# WL-FPGA.net
KiCad netlist of a schematic drawn in Altium Designer
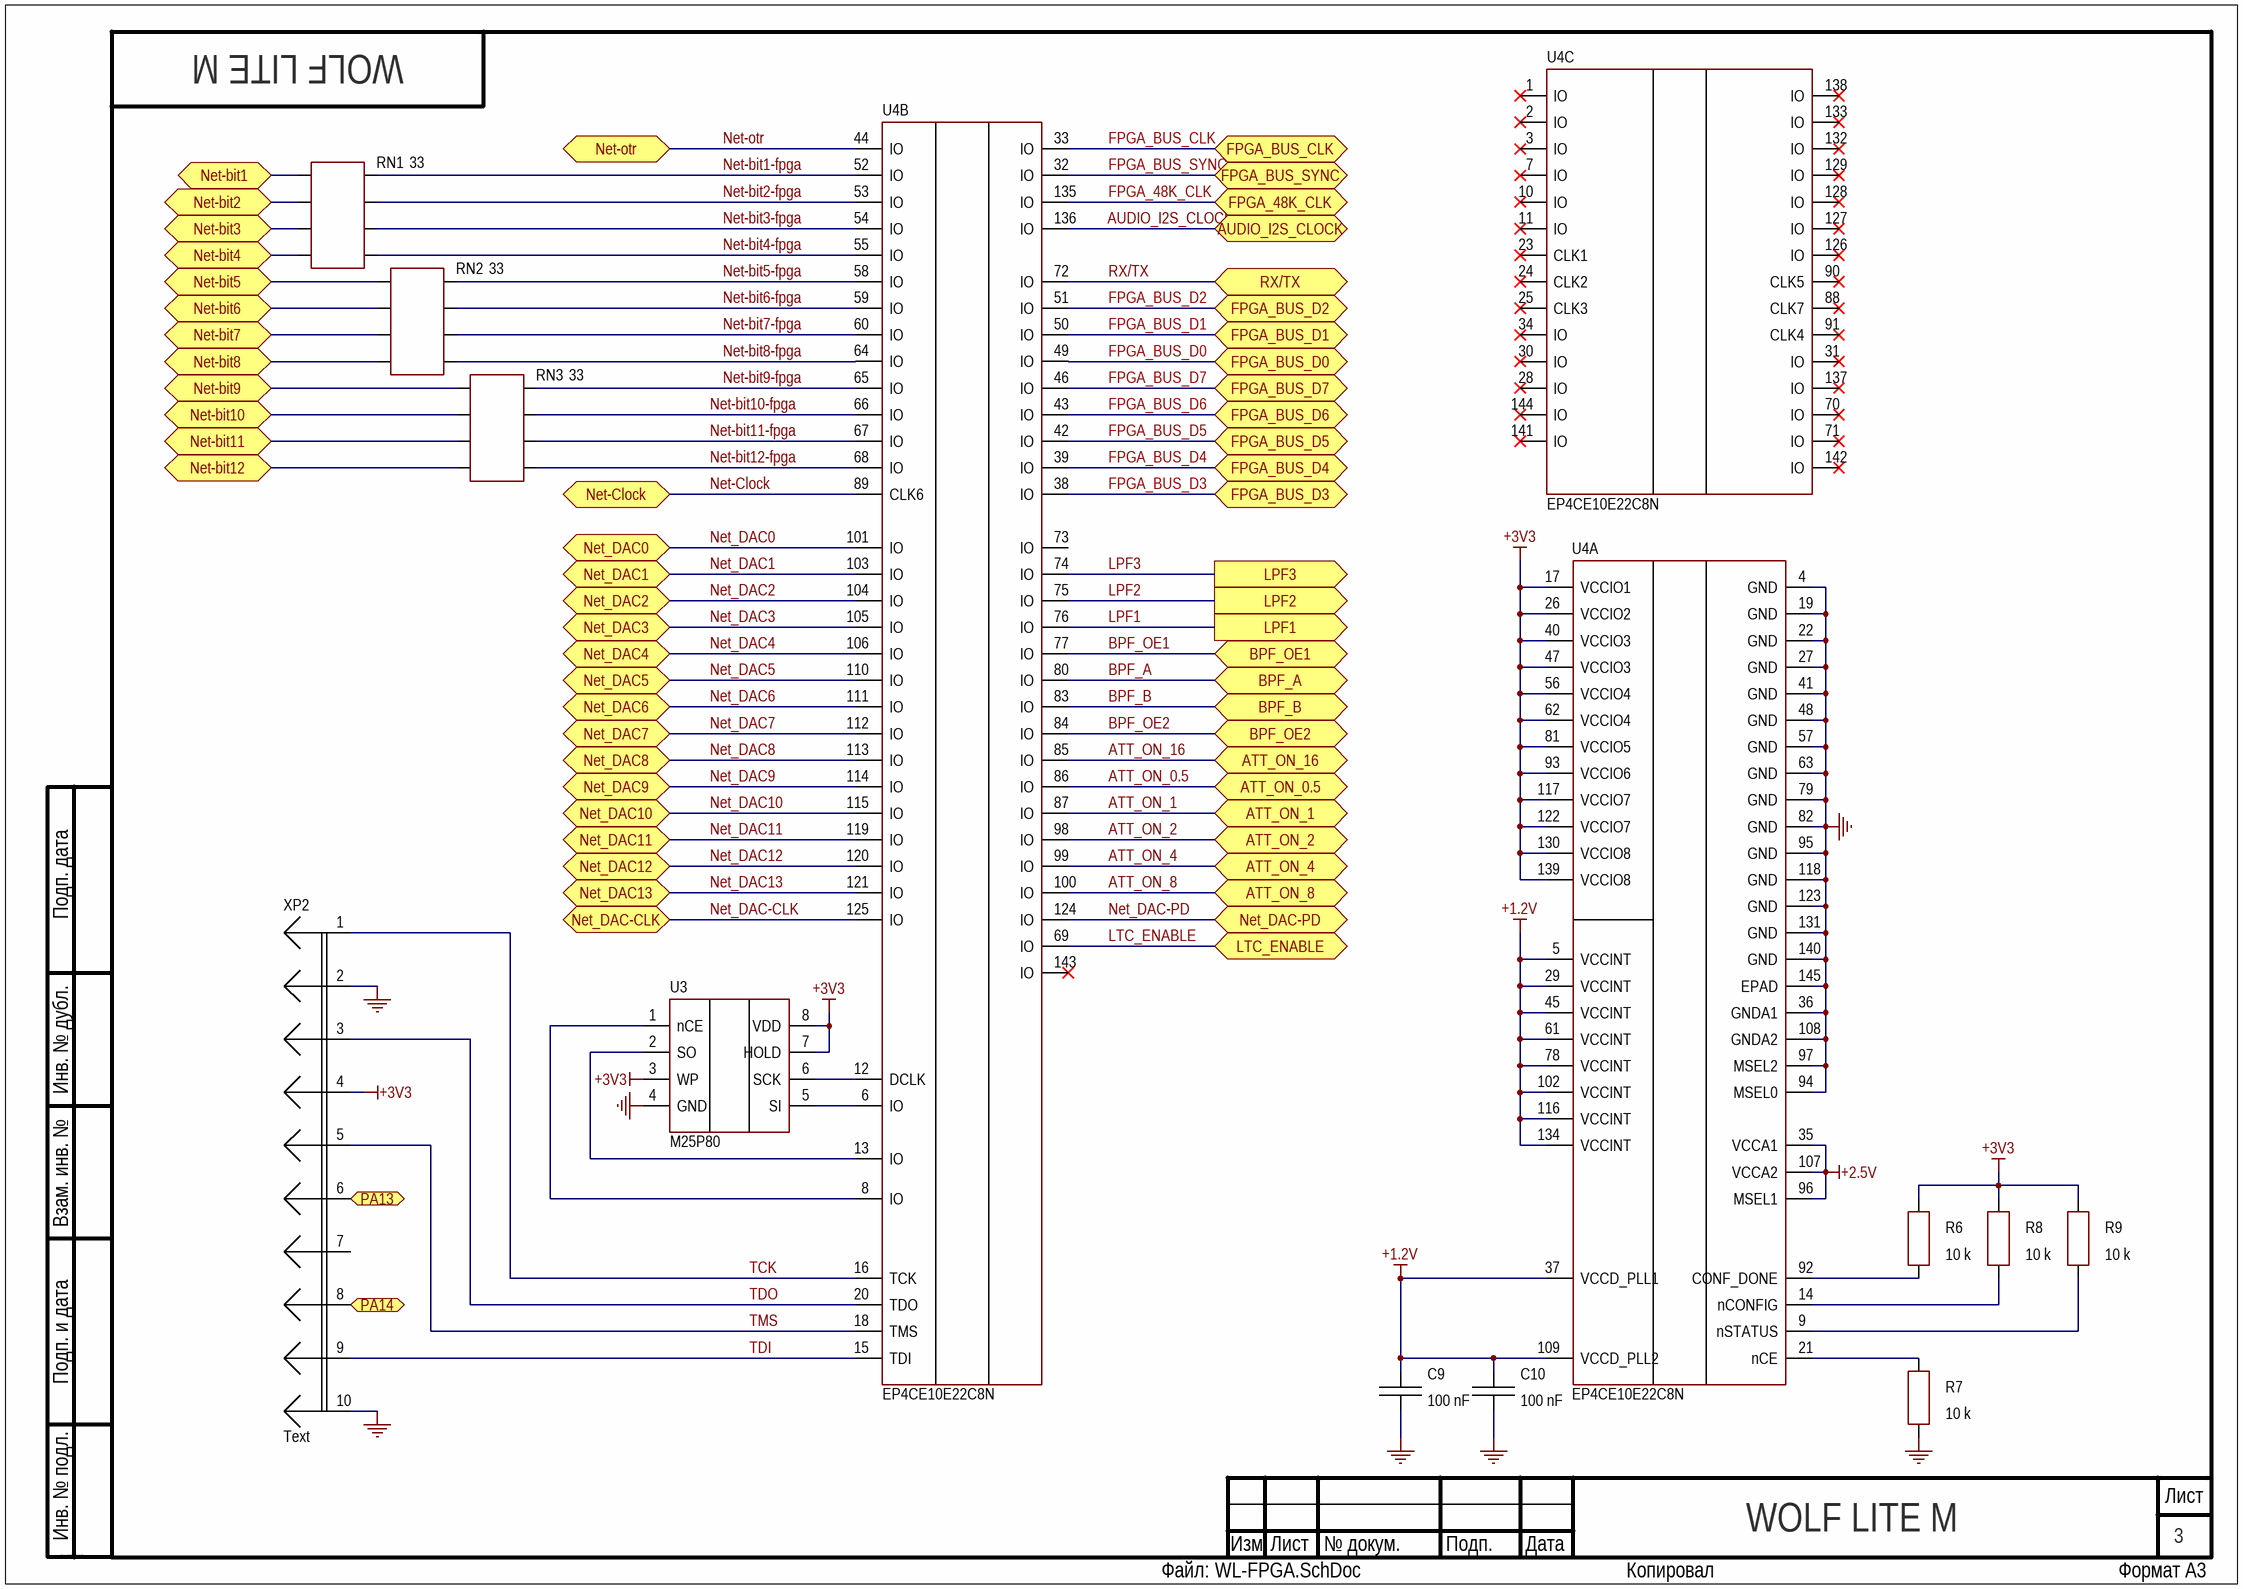
[diagram p0: WL-FPGA.SchDoc]

(export (version "E")
  (design (tool "Eeschema 10.0.6"))
  (components
    (comp (ref "C9")
      (value "100 nF")
      (footprint "C-0805-0.95")
      (fields
        (field (name "MANUFACTURER") "Yageo")
        (field (name "PART NUMBER") "CC0805KRX7R9BB104")
        (field (name "TOLERANCE") "±10%")
      )
      (libsource (lib "GOST") (part "Capacitor"))
    )
    (comp (ref "C10")
      (value "100 nF")
      (footprint "C-0805-0.95")
      (fields
        (field (name "MANUFACTURER") "Yageo")
        (field (name "PART NUMBER") "CC0805KRX7R9BB104")
        (field (name "TOLERANCE") "±10%")
      )
      (libsource (lib "GOST") (part "Capacitor"))
    )
    (comp (ref "R6")
      (value "10 k")
      (footprint "R-0805")
      (fields
        (field (name "MANUFACTURER") "Yageo")
        (field (name "PART NUMBER") "RC0805JR-0710KL")
        (field (name "POWER") "0,125 W")
      )
      (libsource (lib "GOST") (part "Resistor"))
    )
    (comp (ref "R7")
      (value "10 k")
      (footprint "R-0805")
      (fields
        (field (name "MANUFACTURER") "Yageo")
        (field (name "PART NUMBER") "RC0805JR-0710KL")
        (field (name "POWER") "0,125 W")
      )
      (libsource (lib "") (part "Resistor_1"))
    )
    (comp (ref "R8")
      (value "10 k")
      (footprint "R-0805")
      (fields
        (field (name "MANUFACTURER") "Yageo")
        (field (name "PART NUMBER") "RC0805JR-0710KL")
        (field (name "POWER") "0,125 W")
      )
      (libsource (lib "GOST") (part "Resistor"))
    )
    (comp (ref "R9")
      (value "10 k")
      (footprint "R-0805")
      (fields
        (field (name "MANUFACTURER") "Yageo")
        (field (name "PART NUMBER") "RC0805JR-0710KL")
        (field (name "POWER") "0,125 W")
      )
      (libsource (lib "GOST") (part "Resistor"))
    )
    (comp (ref "RN1")
      (value "33")
      (footprint "RN-1206")
      (fields
        (field (name "PART NUMBER") "YC164-JR-0733RL")
        (field (name "POWER") "1/16W")
        (field (name "TOLERANCE") "±5%")
      )
      (libsource (lib "GOST") (part "Resistor array"))
    )
    (comp (ref "RN2")
      (value "33")
      (footprint "RN-1206")
      (fields
        (field (name "PART NUMBER") "YC164-JR-0733RL")
        (field (name "POWER") "1/16W")
        (field (name "TOLERANCE") "±5%")
      )
      (libsource (lib "GOST") (part "Resistor array"))
    )
    (comp (ref "RN3")
      (value "33")
      (footprint "RN-1206")
      (fields
        (field (name "PART NUMBER") "YC164-JR-0733RL")
        (field (name "POWER") "1/16W")
        (field (name "TOLERANCE") "±5%")
      )
      (libsource (lib "GOST") (part "Resistor array"))
    )
    (comp (ref "U3")
      (value "M25P80")
      (footprint "SOIC-8-W")
      (description "IC FLASH 8MBIT SPI 75MHZ")
      (fields
        (field (name "PART NUMBER") "M25P80-VMW6")
        (field (name "MANUFACTURER") "Micron Technology Inc.")
      )
      (libsource (lib "GOST") (part "M25P80-VMN6TPBA TR"))
    )
    (comp (ref "U4")
      (value "EP4CE10E22C8N")
      (footprint "EQFP-144")
      (fields (field (name "MANUFACTURER") "Intel"))
      (libsource (lib "") (part "EP4CE10E22C8N_1"))
    )
    (comp (ref "XP2")
      (value "Text")
      (footprint "PLD-10-JTAG-FPGA-SWD")
      (fields (field (name "PART NUMBER") "PLD-10"))
      (libsource (lib "GOST") (part "Con-10-M"))
    )
  )
  (nets
    (net (code "1") (name "+1.2V") (class "Default")
      (node (ref "C10") (pin "2") (pinfunction "2_2") (pintype "passive"))
      (node (ref "C9") (pin "2") (pinfunction "2_2") (pintype "passive"))
      (node (ref "U4") (pin "102") (pinfunction "VCCINT_102") (pintype "passive"))
      (node (ref "U4") (pin "109") (pinfunction "VCCD_PLL2_109") (pintype "passive"))
      (node (ref "U4") (pin "116") (pinfunction "VCCINT_116") (pintype "passive"))
      (node (ref "U4") (pin "134") (pinfunction "VCCINT_134") (pintype "passive"))
      (node (ref "U4") (pin "29") (pinfunction "VCCINT_29") (pintype "passive"))
      (node (ref "U4") (pin "37") (pinfunction "VCCD_PLL1_37") (pintype "passive"))
      (node (ref "U4") (pin "45") (pinfunction "VCCINT_45") (pintype "passive"))
      (node (ref "U4") (pin "5") (pinfunction "VCCINT_5") (pintype "passive"))
      (node (ref "U4") (pin "61") (pinfunction "VCCINT_61") (pintype "passive"))
      (node (ref "U4") (pin "78") (pinfunction "VCCINT_78") (pintype "passive"))
    )
    (net (code "2") (name "+2.5V") (class "Default")
      (node (ref "U4") (pin "107") (pinfunction "VCCA2_107") (pintype "passive"))
      (node (ref "U4") (pin "35") (pinfunction "VCCA1_35") (pintype "passive"))
      (node (ref "U4") (pin "96") (pinfunction "MSEL1_96") (pintype "passive"))
    )
    (net (code "3") (name "+3V3") (class "Default")
      (node (ref "R6") (pin "1") (pinfunction "1_1") (pintype "passive"))
      (node (ref "R8") (pin "1") (pinfunction "1_1") (pintype "passive"))
      (node (ref "R9") (pin "1") (pinfunction "1_1") (pintype "passive"))
      (node (ref "U3") (pin "3") (pinfunction "WP_3") (pintype "passive"))
      (node (ref "U3") (pin "7") (pinfunction "HOLD_7") (pintype "passive"))
      (node (ref "U3") (pin "8") (pinfunction "VDD_8") (pintype "passive"))
      (node (ref "U4") (pin "117") (pinfunction "VCCIO7_117") (pintype "passive"))
      (node (ref "U4") (pin "122") (pinfunction "VCCIO7_122") (pintype "passive"))
      (node (ref "U4") (pin "130") (pinfunction "VCCIO8_130") (pintype "passive"))
      (node (ref "U4") (pin "139") (pinfunction "VCCIO8_139") (pintype "passive"))
      (node (ref "U4") (pin "17") (pinfunction "VCCIO1_17") (pintype "passive"))
      (node (ref "U4") (pin "26") (pinfunction "VCCIO2_26") (pintype "passive"))
      (node (ref "U4") (pin "40") (pinfunction "VCCIO3_40") (pintype "passive"))
      (node (ref "U4") (pin "47") (pinfunction "VCCIO3_47") (pintype "passive"))
      (node (ref "U4") (pin "56") (pinfunction "VCCIO4_56") (pintype "passive"))
      (node (ref "U4") (pin "62") (pinfunction "VCCIO4_62") (pintype "passive"))
      (node (ref "U4") (pin "81") (pinfunction "VCCIO5_81") (pintype "passive"))
      (node (ref "U4") (pin "93") (pinfunction "VCCIO6_93") (pintype "passive"))
      (node (ref "XP2") (pin "4") (pintype "passive"))
    )
    (net (code "4") (name "/ATT_ON_0.5") (class "Default")
      (node (ref "U4") (pin "86") (pinfunction "IO_86") (pintype "passive"))
    )
    (net (code "5") (name "/ATT_ON_1") (class "Default")
      (node (ref "U4") (pin "87") (pinfunction "IO_87") (pintype "passive"))
    )
    (net (code "6") (name "/ATT_ON_2") (class "Default")
      (node (ref "U4") (pin "98") (pinfunction "IO_98") (pintype "passive"))
    )
    (net (code "7") (name "/ATT_ON_4") (class "Default")
      (node (ref "U4") (pin "99") (pinfunction "IO_99") (pintype "passive"))
    )
    (net (code "8") (name "/ATT_ON_8") (class "Default")
      (node (ref "U4") (pin "100") (pinfunction "IO_100") (pintype "passive"))
    )
    (net (code "9") (name "/ATT_ON_16") (class "Default")
      (node (ref "U4") (pin "85") (pinfunction "IO_85") (pintype "passive"))
    )
    (net (code "10") (name "/AUDIO_I2S_CLOCK") (class "Default")
      (node (ref "U4") (pin "136") (pinfunction "IO_136") (pintype "passive"))
    )
    (net (code "11") (name "/BPF_A") (class "Default")
      (node (ref "U4") (pin "80") (pinfunction "IO_80") (pintype "passive"))
    )
    (net (code "12") (name "/BPF_B") (class "Default")
      (node (ref "U4") (pin "83") (pinfunction "IO_83") (pintype "passive"))
    )
    (net (code "13") (name "/BPF_OE1") (class "Default")
      (node (ref "U4") (pin "77") (pinfunction "IO_77") (pintype "passive"))
    )
    (net (code "14") (name "/BPF_OE2") (class "Default")
      (node (ref "U4") (pin "84") (pinfunction "IO_84") (pintype "passive"))
    )
    (net (code "15") (name "/FPGA_48K_CLK") (class "Default")
      (node (ref "U4") (pin "135") (pinfunction "IO_135") (pintype "passive"))
    )
    (net (code "16") (name "/FPGA_BUS_CLK") (class "Default")
      (node (ref "U4") (pin "33") (pinfunction "IO_33") (pintype "passive"))
    )
    (net (code "17") (name "/FPGA_BUS_D0") (class "Default")
      (node (ref "U4") (pin "49") (pinfunction "IO_49") (pintype "passive"))
    )
    (net (code "18") (name "/FPGA_BUS_D1") (class "Default")
      (node (ref "U4") (pin "50") (pinfunction "IO_50") (pintype "passive"))
    )
    (net (code "19") (name "/FPGA_BUS_D2") (class "Default")
      (node (ref "U4") (pin "51") (pinfunction "IO_51") (pintype "passive"))
    )
    (net (code "20") (name "/FPGA_BUS_D3") (class "Default")
      (node (ref "U4") (pin "38") (pinfunction "IO_38") (pintype "passive"))
    )
    (net (code "21") (name "/FPGA_BUS_D4") (class "Default")
      (node (ref "U4") (pin "39") (pinfunction "IO_39") (pintype "passive"))
    )
    (net (code "22") (name "/FPGA_BUS_D5") (class "Default")
      (node (ref "U4") (pin "42") (pinfunction "IO_42") (pintype "passive"))
    )
    (net (code "23") (name "/FPGA_BUS_D6") (class "Default")
      (node (ref "U4") (pin "43") (pinfunction "IO_43") (pintype "passive"))
    )
    (net (code "24") (name "/FPGA_BUS_D7") (class "Default")
      (node (ref "U4") (pin "46") (pinfunction "IO_46") (pintype "passive"))
    )
    (net (code "25") (name "/FPGA_BUS_SYNC") (class "Default")
      (node (ref "U4") (pin "32") (pinfunction "IO_32") (pintype "passive"))
    )
    (net (code "26") (name "/LPF1") (class "Default")
      (node (ref "U4") (pin "76") (pinfunction "IO_76") (pintype "passive"))
    )
    (net (code "27") (name "/LPF2") (class "Default")
      (node (ref "U4") (pin "75") (pinfunction "IO_75") (pintype "passive"))
    )
    (net (code "28") (name "/LPF3") (class "Default")
      (node (ref "U4") (pin "74") (pinfunction "IO_74") (pintype "passive"))
    )
    (net (code "29") (name "/LTC_ENABLE") (class "Default")
      (node (ref "U4") (pin "69") (pinfunction "IO_69") (pintype "passive"))
    )
    (net (code "30") (name "/Net-Clock") (class "Default")
      (node (ref "U4") (pin "89") (pinfunction "CLK6_89") (pintype "passive"))
    )
    (net (code "31") (name "/Net-bit1") (class "Default")
      (node (ref "RN1") (pin "1") (pinfunction "1_1") (pintype "passive"))
    )
    (net (code "32") (name "/Net-bit1-fpga") (class "Default")
      (node (ref "RN1") (pin "8") (pinfunction "8_8") (pintype "passive"))
      (node (ref "U4") (pin "52") (pinfunction "IO_52") (pintype "passive"))
    )
    (net (code "33") (name "/Net-bit2") (class "Default")
      (node (ref "RN1") (pin "2") (pinfunction "2_2") (pintype "passive"))
    )
    (net (code "34") (name "/Net-bit2-fpga") (class "Default")
      (node (ref "RN1") (pin "7") (pinfunction "7_7") (pintype "passive"))
      (node (ref "U4") (pin "53") (pinfunction "IO_53") (pintype "passive"))
    )
    (net (code "35") (name "/Net-bit3") (class "Default")
      (node (ref "RN1") (pin "3") (pinfunction "3_3") (pintype "passive"))
    )
    (net (code "36") (name "/Net-bit3-fpga") (class "Default")
      (node (ref "RN1") (pin "6") (pinfunction "6_6") (pintype "passive"))
      (node (ref "U4") (pin "54") (pinfunction "IO_54") (pintype "passive"))
    )
    (net (code "37") (name "/Net-bit4") (class "Default")
      (node (ref "RN1") (pin "4") (pinfunction "4_4") (pintype "passive"))
    )
    (net (code "38") (name "/Net-bit4-fpga") (class "Default")
      (node (ref "RN1") (pin "5") (pinfunction "5_5") (pintype "passive"))
      (node (ref "U4") (pin "55") (pinfunction "IO_55") (pintype "passive"))
    )
    (net (code "39") (name "/Net-bit5") (class "Default")
      (node (ref "RN2") (pin "1") (pinfunction "1_1") (pintype "passive"))
    )
    (net (code "40") (name "/Net-bit5-fpga") (class "Default")
      (node (ref "RN2") (pin "8") (pinfunction "8_8") (pintype "passive"))
      (node (ref "U4") (pin "58") (pinfunction "IO_58") (pintype "passive"))
    )
    (net (code "41") (name "/Net-bit6") (class "Default")
      (node (ref "RN2") (pin "2") (pinfunction "2_2") (pintype "passive"))
    )
    (net (code "42") (name "/Net-bit6-fpga") (class "Default")
      (node (ref "RN2") (pin "7") (pinfunction "7_7") (pintype "passive"))
      (node (ref "U4") (pin "59") (pinfunction "IO_59") (pintype "passive"))
    )
    (net (code "43") (name "/Net-bit7") (class "Default")
      (node (ref "RN2") (pin "3") (pinfunction "3_3") (pintype "passive"))
    )
    (net (code "44") (name "/Net-bit7-fpga") (class "Default")
      (node (ref "RN2") (pin "6") (pinfunction "6_6") (pintype "passive"))
      (node (ref "U4") (pin "60") (pinfunction "IO_60") (pintype "passive"))
    )
    (net (code "45") (name "/Net-bit8") (class "Default")
      (node (ref "RN2") (pin "4") (pinfunction "4_4") (pintype "passive"))
    )
    (net (code "46") (name "/Net-bit8-fpga") (class "Default")
      (node (ref "RN2") (pin "5") (pinfunction "5_5") (pintype "passive"))
      (node (ref "U4") (pin "64") (pinfunction "IO_64") (pintype "passive"))
    )
    (net (code "47") (name "/Net-bit9") (class "Default")
      (node (ref "RN3") (pin "1") (pinfunction "1_1") (pintype "passive"))
    )
    (net (code "48") (name "/Net-bit9-fpga") (class "Default")
      (node (ref "RN3") (pin "8") (pinfunction "8_8") (pintype "passive"))
      (node (ref "U4") (pin "65") (pinfunction "IO_65") (pintype "passive"))
    )
    (net (code "49") (name "/Net-bit10") (class "Default")
      (node (ref "RN3") (pin "2") (pinfunction "2_2") (pintype "passive"))
    )
    (net (code "50") (name "/Net-bit10-fpga") (class "Default")
      (node (ref "RN3") (pin "7") (pinfunction "7_7") (pintype "passive"))
      (node (ref "U4") (pin "66") (pinfunction "IO_66") (pintype "passive"))
    )
    (net (code "51") (name "/Net-bit11") (class "Default")
      (node (ref "RN3") (pin "3") (pinfunction "3_3") (pintype "passive"))
    )
    (net (code "52") (name "/Net-bit11-fpga") (class "Default")
      (node (ref "RN3") (pin "6") (pinfunction "6_6") (pintype "passive"))
      (node (ref "U4") (pin "67") (pinfunction "IO_67") (pintype "passive"))
    )
    (net (code "53") (name "/Net-bit12") (class "Default")
      (node (ref "RN3") (pin "4") (pinfunction "4_4") (pintype "passive"))
    )
    (net (code "54") (name "/Net-bit12-fpga") (class "Default")
      (node (ref "RN3") (pin "5") (pinfunction "5_5") (pintype "passive"))
      (node (ref "U4") (pin "68") (pinfunction "IO_68") (pintype "passive"))
    )
    (net (code "55") (name "/Net-otr") (class "Default")
      (node (ref "U4") (pin "44") (pinfunction "IO_44") (pintype "passive"))
    )
    (net (code "56") (name "/Net_DAC-CLK") (class "Default")
      (node (ref "U4") (pin "125") (pinfunction "IO_125") (pintype "passive"))
    )
    (net (code "57") (name "/Net_DAC-PD") (class "Default")
      (node (ref "U4") (pin "124") (pinfunction "IO_124") (pintype "passive"))
    )
    (net (code "58") (name "/Net_DAC0") (class "Default")
      (node (ref "U4") (pin "101") (pinfunction "IO_101") (pintype "passive"))
    )
    (net (code "59") (name "/Net_DAC1") (class "Default")
      (node (ref "U4") (pin "103") (pinfunction "IO_103") (pintype "passive"))
    )
    (net (code "60") (name "/Net_DAC2") (class "Default")
      (node (ref "U4") (pin "104") (pinfunction "IO_104") (pintype "passive"))
    )
    (net (code "61") (name "/Net_DAC3") (class "Default")
      (node (ref "U4") (pin "105") (pinfunction "IO_105") (pintype "passive"))
    )
    (net (code "62") (name "/Net_DAC4") (class "Default")
      (node (ref "U4") (pin "106") (pinfunction "IO_106") (pintype "passive"))
    )
    (net (code "63") (name "/Net_DAC5") (class "Default")
      (node (ref "U4") (pin "110") (pinfunction "IO_110") (pintype "passive"))
    )
    (net (code "64") (name "/Net_DAC6") (class "Default")
      (node (ref "U4") (pin "111") (pinfunction "IO_111") (pintype "passive"))
    )
    (net (code "65") (name "/Net_DAC7") (class "Default")
      (node (ref "U4") (pin "112") (pinfunction "IO_112") (pintype "passive"))
    )
    (net (code "66") (name "/Net_DAC8") (class "Default")
      (node (ref "U4") (pin "113") (pinfunction "IO_113") (pintype "passive"))
    )
    (net (code "67") (name "/Net_DAC9") (class "Default")
      (node (ref "U4") (pin "114") (pinfunction "IO_114") (pintype "passive"))
    )
    (net (code "68") (name "/Net_DAC10") (class "Default")
      (node (ref "U4") (pin "115") (pinfunction "IO_115") (pintype "passive"))
    )
    (net (code "69") (name "/Net_DAC11") (class "Default")
      (node (ref "U4") (pin "119") (pinfunction "IO_119") (pintype "passive"))
    )
    (net (code "70") (name "/Net_DAC12") (class "Default")
      (node (ref "U4") (pin "120") (pinfunction "IO_120") (pintype "passive"))
    )
    (net (code "71") (name "/Net_DAC13") (class "Default")
      (node (ref "U4") (pin "121") (pinfunction "IO_121") (pintype "passive"))
    )
    (net (code "72") (name "/PA13") (class "Default") (node (ref "XP2") (pin "6") (pintype "passive")))
    (net (code "73") (name "/PA14") (class "Default") (node (ref "XP2") (pin "8") (pintype "passive")))
    (net (code "74") (name "/RX{slash}TX") (class "Default")
      (node (ref "U4") (pin "72") (pinfunction "IO_72") (pintype "passive"))
    )
    (net (code "75") (name "/TCK") (class "Default")
      (node (ref "U4") (pin "16") (pinfunction "TCK_16") (pintype "passive"))
      (node (ref "XP2") (pin "1") (pintype "passive"))
    )
    (net (code "76") (name "/TDI") (class "Default")
      (node (ref "U4") (pin "15") (pinfunction "TDI_15") (pintype "power_in"))
      (node (ref "XP2") (pin "9") (pintype "passive"))
    )
    (net (code "77") (name "/TDO") (class "Default")
      (node (ref "U4") (pin "20") (pinfunction "TDO_20") (pintype "passive"))
      (node (ref "XP2") (pin "3") (pintype "passive"))
    )
    (net (code "78") (name "/TMS") (class "Default")
      (node (ref "U4") (pin "18") (pinfunction "TMS_18") (pintype "passive"))
      (node (ref "XP2") (pin "5") (pintype "passive"))
    )
    (net (code "79") (name "GND") (class "Default")
      (node (ref "C10") (pin "1") (pinfunction "1_1") (pintype "passive"))
      (node (ref "C9") (pin "1") (pinfunction "1_1") (pintype "passive"))
      (node (ref "R7") (pin "1") (pinfunction "1_1") (pintype "passive"))
      (node (ref "U3") (pin "4") (pinfunction "GND_4") (pintype "passive"))
      (node (ref "U4") (pin "108") (pinfunction "GNDA2_108") (pintype "passive"))
      (node (ref "U4") (pin "118") (pinfunction "GND_118") (pintype "passive"))
      (node (ref "U4") (pin "123") (pinfunction "GND_123") (pintype "passive"))
      (node (ref "U4") (pin "131") (pinfunction "GND_131") (pintype "passive"))
      (node (ref "U4") (pin "140") (pinfunction "GND_140") (pintype "passive"))
      (node (ref "U4") (pin "145") (pinfunction "EPAD_145") (pintype "passive"))
      (node (ref "U4") (pin "19") (pinfunction "GND_19") (pintype "passive"))
      (node (ref "U4") (pin "22") (pinfunction "GND_22") (pintype "passive"))
      (node (ref "U4") (pin "27") (pinfunction "GND_27") (pintype "passive"))
      (node (ref "U4") (pin "36") (pinfunction "GNDA1_36") (pintype "passive"))
      (node (ref "U4") (pin "4") (pinfunction "GND_4") (pintype "passive"))
      (node (ref "U4") (pin "41") (pinfunction "GND_41") (pintype "passive"))
      (node (ref "U4") (pin "48") (pinfunction "GND_48") (pintype "passive"))
      (node (ref "U4") (pin "57") (pinfunction "GND_57") (pintype "passive"))
      (node (ref "U4") (pin "63") (pinfunction "GND_63") (pintype "passive"))
      (node (ref "U4") (pin "79") (pinfunction "GND_79") (pintype "passive"))
      (node (ref "U4") (pin "82") (pinfunction "GND_82") (pintype "passive"))
      (node (ref "U4") (pin "94") (pinfunction "MSEL0_94") (pintype "passive"))
      (node (ref "U4") (pin "95") (pinfunction "GND_95") (pintype "passive"))
      (node (ref "U4") (pin "97") (pinfunction "MSEL2_97") (pintype "passive"))
      (node (ref "XP2") (pin "10") (pintype "passive"))
      (node (ref "XP2") (pin "2") (pintype "passive"))
    )
    (net (code "80") (name "Net-(U3-SCK)") (class "Default")
      (node (ref "U3") (pin "6") (pinfunction "SCK_6") (pintype "passive"))
      (node (ref "U4") (pin "12") (pinfunction "DCLK_12") (pintype "passive"))
    )
    (net (code "81") (name "Net-(U3-SI)") (class "Default")
      (node (ref "U3") (pin "5") (pinfunction "SI_5") (pintype "passive"))
      (node (ref "U4") (pin "6") (pinfunction "IO_6") (pintype "passive"))
    )
    (net (code "82") (name "Net-(U3-SO)") (class "Default")
      (node (ref "U3") (pin "2") (pinfunction "SO_2") (pintype "passive"))
      (node (ref "U4") (pin "13") (pinfunction "IO_13") (pintype "passive"))
    )
    (net (code "83") (name "Net-(U3-nCE)") (class "Default")
      (node (ref "U3") (pin "1") (pinfunction "nCE_1") (pintype "passive"))
      (node (ref "U4") (pin "8") (pinfunction "IO_8") (pintype "passive"))
    )
    (net (code "84") (name "Net-(U4A-CONF_DONE)") (class "Default")
      (node (ref "R6") (pin "2") (pinfunction "2_2") (pintype "passive"))
      (node (ref "U4") (pin "92") (pinfunction "CONF_DONE_92") (pintype "passive"))
    )
    (net (code "85") (name "Net-(U4A-nCE)") (class "Default")
      (node (ref "R7") (pin "2") (pinfunction "2_2") (pintype "passive"))
      (node (ref "U4") (pin "21") (pinfunction "nCE_21") (pintype "passive"))
    )
    (net (code "86") (name "Net-(U4A-nCONFIG)") (class "Default")
      (node (ref "R8") (pin "2") (pinfunction "2_2") (pintype "passive"))
      (node (ref "U4") (pin "14") (pinfunction "nCONFIG_14") (pintype "passive"))
    )
    (net (code "87") (name "Net-(U4A-nSTATUS)") (class "Default")
      (node (ref "R9") (pin "2") (pinfunction "2_2") (pintype "passive"))
      (node (ref "U4") (pin "9") (pinfunction "nSTATUS_9") (pintype "passive"))
    )
    (net (code "88") (name "unconnected-(U4B-IO-Pad73)") (class "Default")
      (node (ref "U4") (pin "73") (pinfunction "IO_73") (pintype "passive"))
    )
    (net (code "89") (name "unconnected-(U4B-IO-Pad143)") (class "Default")
      (node (ref "U4") (pin "143") (pinfunction "IO_143") (pintype "passive"))
    )
    (net (code "90") (name "unconnected-(U4C-CLK1-Pad23)") (class "Default")
      (node (ref "U4") (pin "23") (pinfunction "CLK1_23") (pintype "passive+no_connect"))
    )
    (net (code "91") (name "unconnected-(U4C-CLK2-Pad24)") (class "Default")
      (node (ref "U4") (pin "24") (pinfunction "CLK2_24") (pintype "passive+no_connect"))
    )
    (net (code "92") (name "unconnected-(U4C-CLK3-Pad25)") (class "Default")
      (node (ref "U4") (pin "25") (pinfunction "CLK3_25") (pintype "passive+no_connect"))
    )
    (net (code "93") (name "unconnected-(U4C-CLK4-Pad91)") (class "Default")
      (node (ref "U4") (pin "91") (pinfunction "CLK4_91") (pintype "passive+no_connect"))
    )
    (net (code "94") (name "unconnected-(U4C-CLK5-Pad90)") (class "Default")
      (node (ref "U4") (pin "90") (pinfunction "CLK5_90") (pintype "passive+no_connect"))
    )
    (net (code "95") (name "unconnected-(U4C-CLK7-Pad88)") (class "Default")
      (node (ref "U4") (pin "88") (pinfunction "CLK7_88") (pintype "passive+no_connect"))
    )
    (net (code "96") (name "unconnected-(U4C-IO-Pad1)") (class "Default")
      (node (ref "U4") (pin "1") (pinfunction "IO_1") (pintype "passive+no_connect"))
    )
    (net (code "97") (name "unconnected-(U4C-IO-Pad2)") (class "Default")
      (node (ref "U4") (pin "2") (pinfunction "IO_2") (pintype "passive+no_connect"))
    )
    (net (code "98") (name "unconnected-(U4C-IO-Pad3)") (class "Default")
      (node (ref "U4") (pin "3") (pinfunction "IO_3") (pintype "passive+no_connect"))
    )
    (net (code "99") (name "unconnected-(U4C-IO-Pad7)") (class "Default")
      (node (ref "U4") (pin "7") (pinfunction "IO_7") (pintype "passive+no_connect"))
    )
    (net (code "100") (name "unconnected-(U4C-IO-Pad10)") (class "Default")
      (node (ref "U4") (pin "10") (pinfunction "IO_10") (pintype "passive+no_connect"))
    )
    (net (code "101") (name "unconnected-(U4C-IO-Pad11)") (class "Default")
      (node (ref "U4") (pin "11") (pinfunction "IO_11") (pintype "passive+no_connect"))
    )
    (net (code "102") (name "unconnected-(U4C-IO-Pad28)") (class "Default")
      (node (ref "U4") (pin "28") (pinfunction "IO_28") (pintype "passive+no_connect"))
    )
    (net (code "103") (name "unconnected-(U4C-IO-Pad30)") (class "Default")
      (node (ref "U4") (pin "30") (pinfunction "IO_30") (pintype "passive+no_connect"))
    )
    (net (code "104") (name "unconnected-(U4C-IO-Pad31)") (class "Default")
      (node (ref "U4") (pin "31") (pinfunction "IO_31") (pintype "passive+no_connect"))
    )
    (net (code "105") (name "unconnected-(U4C-IO-Pad34)") (class "Default")
      (node (ref "U4") (pin "34") (pinfunction "IO_34") (pintype "passive+no_connect"))
    )
    (net (code "106") (name "unconnected-(U4C-IO-Pad70)") (class "Default")
      (node (ref "U4") (pin "70") (pinfunction "IO_70") (pintype "passive+no_connect"))
    )
    (net (code "107") (name "unconnected-(U4C-IO-Pad71)") (class "Default")
      (node (ref "U4") (pin "71") (pinfunction "IO_71") (pintype "passive+no_connect"))
    )
    (net (code "108") (name "unconnected-(U4C-IO-Pad126)") (class "Default")
      (node (ref "U4") (pin "126") (pinfunction "IO_126") (pintype "passive+no_connect"))
    )
    (net (code "109") (name "unconnected-(U4C-IO-Pad127)") (class "Default")
      (node (ref "U4") (pin "127") (pinfunction "IO_127") (pintype "passive+no_connect"))
    )
    (net (code "110") (name "unconnected-(U4C-IO-Pad128)") (class "Default")
      (node (ref "U4") (pin "128") (pinfunction "IO_128") (pintype "passive+no_connect"))
    )
    (net (code "111") (name "unconnected-(U4C-IO-Pad129)") (class "Default")
      (node (ref "U4") (pin "129") (pinfunction "IO_129") (pintype "passive+no_connect"))
    )
    (net (code "112") (name "unconnected-(U4C-IO-Pad132)") (class "Default")
      (node (ref "U4") (pin "132") (pinfunction "IO_132") (pintype "passive+no_connect"))
    )
    (net (code "113") (name "unconnected-(U4C-IO-Pad133)") (class "Default")
      (node (ref "U4") (pin "133") (pinfunction "IO_133") (pintype "passive+no_connect"))
    )
    (net (code "114") (name "unconnected-(U4C-IO-Pad137)") (class "Default")
      (node (ref "U4") (pin "137") (pinfunction "IO_137") (pintype "passive+no_connect"))
    )
    (net (code "115") (name "unconnected-(U4C-IO-Pad138)") (class "Default")
      (node (ref "U4") (pin "138") (pinfunction "IO_138") (pintype "passive+no_connect"))
    )
    (net (code "116") (name "unconnected-(U4C-IO-Pad141)") (class "Default")
      (node (ref "U4") (pin "141") (pinfunction "IO_141") (pintype "passive+no_connect"))
    )
    (net (code "117") (name "unconnected-(U4C-IO-Pad142)") (class "Default")
      (node (ref "U4") (pin "142") (pinfunction "IO_142") (pintype "passive+no_connect"))
    )
    (net (code "118") (name "unconnected-(U4C-IO-Pad144)") (class "Default")
      (node (ref "U4") (pin "144") (pinfunction "IO_144") (pintype "passive+no_connect"))
    )
    (net (code "119") (name "unconnected-(XP2-Pad7)") (class "Default")
      (node (ref "XP2") (pin "7") (pintype "passive"))
    )
  )
)
